# 1_P2.net
KiCad netlist of a schematic drawn in Altium Designer
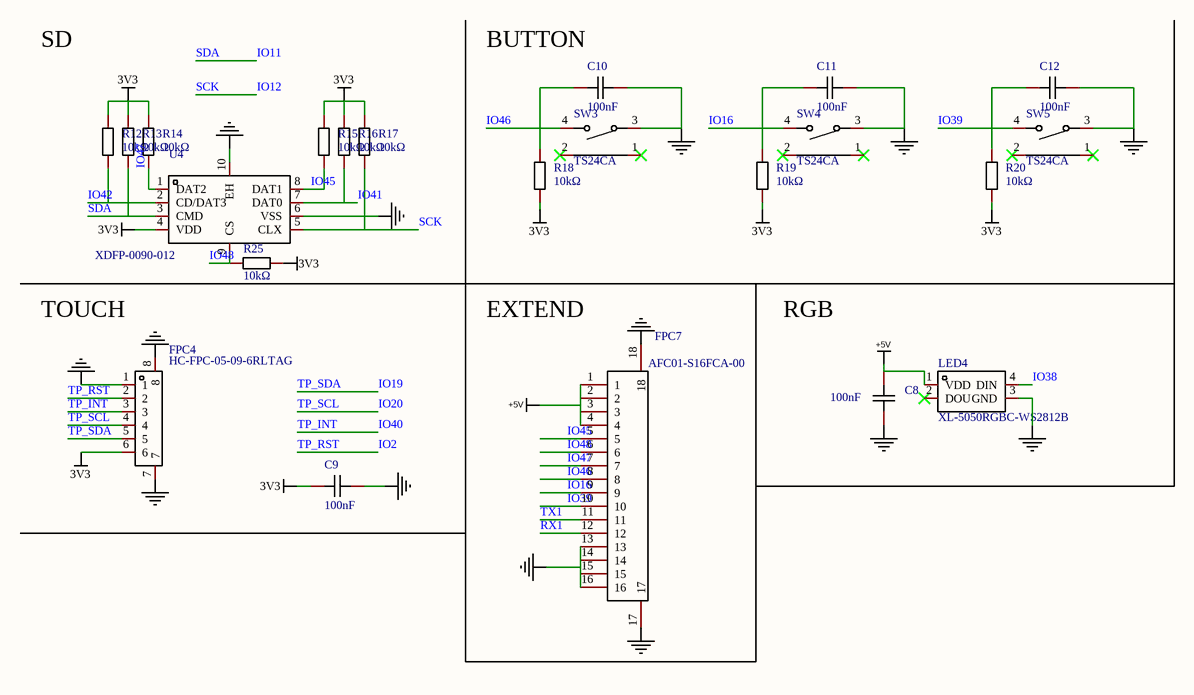
[diagram p0: 1_P2.schdoc]

(export (version "E")
  (design (tool "Eeschema 10.0.6"))
  (components
    (comp (ref "C8")
      (value "100nF")
      (description "容值:100nF;精度:±10%;额定电压:50V;材质(温度系数):X7R;")
      (fields
        (field (name "NAME") "100nF")
        (field (name "MANUFACTURER") "YAGEO(国巨)")
        (field (name "MANUFACTURER PART") "CC0603KRX7R9BB104")
      )
      (libsource (lib "altium-import") (part "root_1_CC0603KRX7R9BB104_"))
    )
    (comp (ref "C9")
      (value "100nF")
      (description "容值:100nF;精度:±10%;额定电压:50V;材质(温度系数):X7R;")
      (fields
        (field (name "NAME") "100nF")
        (field (name "MANUFACTURER") "YAGEO(国巨)")
        (field (name "MANUFACTURER PART") "CC0603KRX7R9BB104")
      )
      (libsource (lib "altium-import") (part "root_2_CC0603KRX7R9BB104_"))
    )
    (comp (ref "C10")
      (value "100nF")
      (description "容值:100nF;精度:±10%;额定电压:50V;材质(温度系数):X7R;")
      (fields
        (field (name "NAME") "100nF")
        (field (name "MANUFACTURER") "YAGEO(国巨)")
        (field (name "MANUFACTURER PART") "CC0603KRX7R9BB104")
      )
      (libsource (lib "altium-import") (part "root_0_CC0603KRX7R9BB104_"))
    )
    (comp (ref "C11")
      (value "100nF")
      (description "容值:100nF;精度:±10%;额定电压:50V;材质(温度系数):X7R;")
      (fields
        (field (name "NAME") "100nF")
        (field (name "MANUFACTURER") "YAGEO(国巨)")
        (field (name "MANUFACTURER PART") "CC0603KRX7R9BB104")
      )
      (libsource (lib "altium-import") (part "root_0_CC0603KRX7R9BB104_"))
    )
    (comp (ref "C12")
      (value "100nF")
      (description "容值:100nF;精度:±10%;额定电压:50V;材质(温度系数):X7R;")
      (fields
        (field (name "NAME") "100nF")
        (field (name "MANUFACTURER") "YAGEO(国巨)")
        (field (name "MANUFACTURER PART") "CC0603KRX7R9BB104")
      )
      (libsource (lib "altium-import") (part "root_0_CC0603KRX7R9BB104_"))
    )
    (comp (ref "FPC4")
      (value "HC-FPC-05-09-6RLTAG")
      (description "锁定特性:翻盖式;触点类型:双侧触点/上下接;触点数量:6P;间距:0.5mm;安装类型:卧贴;工作温度范围:-55℃~+85℃;")
      (fields (field (name "NAME") "HC-FPC-05-09-6RLTAG") (field (name "MANUFACTURER") "HCTL(华灿天禄)"))
      (libsource (lib "altium-import") (part "root_0_HC-FPC-05-09-6RLTAG_"))
    )
    (comp (ref "FPC7")
      (value "AFC01-S16FCA-00")
      (description "锁定特性:翻盖式;触点类型:下接;触点数量:16P;间距:0.5mm;安装类型:卧贴;")
      (fields (field (name "NAME") "AFC01-S16FCA-00") (field (name "MANUFACTURER") "JS(钜硕电子)"))
      (libsource (lib "altium-import") (part "root_0_AFC01-S16FCA-00_"))
    )
    (comp (ref "LED4")
      (value "XL-5050RGBC-WS2812B")
      (description "5050七彩幻彩透明贴片LED灯珠 5050 幻彩透明四脚 ws2812B 内置驱动IC")
      (fields (field (name "NAME") "XL-5050RGBC-WS2812B") (field (name "MANUFACTURER") "XINGLIGHT(成兴光)"))
      (libsource (lib "altium-import") (part "root_0_XL-5050RGBC-WS2812B_"))
    )
    (comp (ref "R12")
      (value "10kΩ")
      (description "电阻类型:厚膜电阻;阻值:10kΩ;精度:±1%;功率:100mW;最大工作电压:75V;温度系数:±100ppm/℃;")
      (fields
        (field (name "NAME") "10kΩ")
        (field (name "MANUFACTURER") "UNI-ROYAL(厚声)")
        (field (name "MANUFACTURER PART") "0603WAF1002T5E")
      )
      (libsource (lib "altium-import") (part "root_1_0603WAF1002T5E_"))
    )
    (comp (ref "R13")
      (value "10kΩ")
      (description "电阻类型:厚膜电阻;阻值:10kΩ;精度:±1%;功率:100mW;最大工作电压:75V;温度系数:±100ppm/℃;")
      (fields
        (field (name "NAME") "10kΩ")
        (field (name "MANUFACTURER") "UNI-ROYAL(厚声)")
        (field (name "MANUFACTURER PART") "0603WAF1002T5E")
      )
      (libsource (lib "altium-import") (part "root_1_0603WAF1002T5E_"))
    )
    (comp (ref "R14")
      (value "10kΩ")
      (description "电阻类型:厚膜电阻;阻值:10kΩ;精度:±1%;功率:100mW;最大工作电压:75V;温度系数:±100ppm/℃;")
      (fields
        (field (name "NAME") "10kΩ")
        (field (name "MANUFACTURER") "UNI-ROYAL(厚声)")
        (field (name "MANUFACTURER PART") "0603WAF1002T5E")
      )
      (libsource (lib "altium-import") (part "root_1_0603WAF1002T5E_"))
    )
    (comp (ref "R15")
      (value "10kΩ")
      (description "电阻类型:厚膜电阻;阻值:10kΩ;精度:±1%;功率:100mW;最大工作电压:75V;温度系数:±100ppm/℃;")
      (fields
        (field (name "NAME") "10kΩ")
        (field (name "MANUFACTURER") "UNI-ROYAL(厚声)")
        (field (name "MANUFACTURER PART") "0603WAF1002T5E")
      )
      (libsource (lib "altium-import") (part "root_1_0603WAF1002T5E_"))
    )
    (comp (ref "R16")
      (value "10kΩ")
      (description "电阻类型:厚膜电阻;阻值:10kΩ;精度:±1%;功率:100mW;最大工作电压:75V;温度系数:±100ppm/℃;")
      (fields
        (field (name "NAME") "10kΩ")
        (field (name "MANUFACTURER") "UNI-ROYAL(厚声)")
        (field (name "MANUFACTURER PART") "0603WAF1002T5E")
      )
      (libsource (lib "altium-import") (part "root_1_0603WAF1002T5E_"))
    )
    (comp (ref "R17")
      (value "10kΩ")
      (description "电阻类型:厚膜电阻;阻值:10kΩ;精度:±1%;功率:100mW;最大工作电压:75V;温度系数:±100ppm/℃;")
      (fields
        (field (name "NAME") "10kΩ")
        (field (name "MANUFACTURER") "UNI-ROYAL(厚声)")
        (field (name "MANUFACTURER PART") "0603WAF1002T5E")
      )
      (libsource (lib "altium-import") (part "root_1_0603WAF1002T5E_"))
    )
    (comp (ref "R18")
      (value "10kΩ")
      (description "电阻类型:厚膜电阻;阻值:10kΩ;精度:±1%;功率:100mW;最大工作电压:75V;温度系数:±100ppm/℃;")
      (fields
        (field (name "NAME") "10kΩ")
        (field (name "MANUFACTURER") "UNI-ROYAL(厚声)")
        (field (name "MANUFACTURER PART") "0603WAF1002T5E")
      )
      (libsource (lib "altium-import") (part "root_1_0603WAF1002T5E_"))
    )
    (comp (ref "R19")
      (value "10kΩ")
      (description "电阻类型:厚膜电阻;阻值:10kΩ;精度:±1%;功率:100mW;最大工作电压:75V;温度系数:±100ppm/℃;")
      (fields
        (field (name "NAME") "10kΩ")
        (field (name "MANUFACTURER") "UNI-ROYAL(厚声)")
        (field (name "MANUFACTURER PART") "0603WAF1002T5E")
      )
      (libsource (lib "altium-import") (part "root_1_0603WAF1002T5E_"))
    )
    (comp (ref "R20")
      (value "10kΩ")
      (description "电阻类型:厚膜电阻;阻值:10kΩ;精度:±1%;功率:100mW;最大工作电压:75V;温度系数:±100ppm/℃;")
      (fields
        (field (name "NAME") "10kΩ")
        (field (name "MANUFACTURER") "UNI-ROYAL(厚声)")
        (field (name "MANUFACTURER PART") "0603WAF1002T5E")
      )
      (libsource (lib "altium-import") (part "root_1_0603WAF1002T5E_"))
    )
    (comp (ref "R25")
      (value "10kΩ")
      (description "电阻类型:厚膜电阻;阻值:10kΩ;精度:±1%;功率:100mW;最大工作电压:75V;温度系数:±100ppm/℃;")
      (fields
        (field (name "NAME") "10kΩ")
        (field (name "MANUFACTURER") "UNI-ROYAL(厚声)")
        (field (name "MANUFACTURER PART") "0603WAF1002T5E")
      )
      (libsource (lib "altium-import") (part "root_2_0603WAF1002T5E_"))
    )
    (comp (ref "SW3")
      (value "TS24CA")
      (description "电路结构:单刀单掷;按钮形状:矩形按钮;安装方式:卧贴;开关长度:4.55mm;开关宽度:1.8mm;开关高度:3.5mm;触点电流:50mA;额定电压(DC):12V;带灯:-;机械寿命:-;")
      (fields (field (name "NAME") "TS24CA") (field (name "MANUFACTURER") "SHOU HAN(首韩)"))
      (libsource (lib "altium-import") (part "root_2_TS24CA_"))
    )
    (comp (ref "SW4")
      (value "TS24CA")
      (description "电路结构:单刀单掷;按钮形状:矩形按钮;安装方式:卧贴;开关长度:4.55mm;开关宽度:1.8mm;开关高度:3.5mm;触点电流:50mA;额定电压(DC):12V;带灯:-;机械寿命:-;")
      (fields (field (name "NAME") "TS24CA") (field (name "MANUFACTURER") "SHOU HAN(首韩)"))
      (libsource (lib "altium-import") (part "root_2_TS24CA_"))
    )
    (comp (ref "SW5")
      (value "TS24CA")
      (description "电路结构:单刀单掷;按钮形状:矩形按钮;安装方式:卧贴;开关长度:4.55mm;开关宽度:1.8mm;开关高度:3.5mm;触点电流:50mA;额定电压(DC):12V;带灯:-;机械寿命:-;")
      (fields (field (name "NAME") "TS24CA") (field (name "MANUFACTURER") "SHOU HAN(首韩)"))
      (libsource (lib "altium-import") (part "root_2_TS24CA_"))
    )
    (comp (ref "U4")
      (value "XDFP-0090-012")
      (description "卡连接方式:自弹式;本体最大高度:1.85mm;触头镀层:金;")
      (fields (field (name "NAME") "XDFP-0090-012") (field (name "MANUFACTURER") "LX(连欣科技)"))
      (libsource (lib "altium-import") (part "root_0_XDFP-0090-012_"))
    )
  )
  (nets
    (net (code "1") (name "+5V") (class "Default")
      (node (ref "C8") (pin "2") (pinfunction "2_2") (pintype "passive"))
      (node (ref "FPC7") (pin "1") (pinfunction "1_1") (pintype "passive"))
      (node (ref "FPC7") (pin "2") (pinfunction "2_2") (pintype "passive"))
      (node (ref "FPC7") (pin "3") (pinfunction "3_3") (pintype "passive"))
      (node (ref "FPC7") (pin "4") (pinfunction "4_4") (pintype "passive"))
      (node (ref "LED4") (pin "1") (pinfunction "VDD_1") (pintype "passive"))
    )
    (net (code "2") (name "/IO2") (class "Default")
      (node (ref "FPC4") (pin "2") (pinfunction "2_2") (pintype "passive"))
    )
    (net (code "3") (name "/IO11") (class "Default")
      (node (ref "R13") (pin "1") (pinfunction "1_1") (pintype "passive"))
      (node (ref "U4") (pin "3") (pinfunction "CMD_3") (pintype "passive"))
    )
    (net (code "4") (name "/IO12") (class "Default")
      (node (ref "R17") (pin "1") (pinfunction "1_1") (pintype "passive"))
      (node (ref "U4") (pin "5") (pinfunction "CLX_5") (pintype "passive"))
    )
    (net (code "5") (name "/IO16") (class "Default")
      (node (ref "C11") (pin "1") (pinfunction "1_1") (pintype "passive"))
      (node (ref "FPC7") (pin "9") (pinfunction "9_9") (pintype "passive"))
      (node (ref "R19") (pin "2") (pinfunction "2_2") (pintype "passive"))
      (node (ref "SW4") (pin "4") (pinfunction "4_4") (pintype "passive"))
    )
    (net (code "6") (name "/IO19") (class "Default")
      (node (ref "FPC4") (pin "5") (pinfunction "5_5") (pintype "passive"))
    )
    (net (code "7") (name "/IO20") (class "Default")
      (node (ref "FPC4") (pin "4") (pinfunction "4_4") (pintype "passive"))
    )
    (net (code "8") (name "/IO38") (class "Default")
      (node (ref "LED4") (pin "4") (pinfunction "DIN_4") (pintype "passive"))
    )
    (net (code "9") (name "/IO39") (class "Default")
      (node (ref "C12") (pin "1") (pinfunction "1_1") (pintype "passive"))
      (node (ref "FPC7") (pin "10") (pinfunction "10_10") (pintype "passive"))
      (node (ref "R20") (pin "2") (pinfunction "2_2") (pintype "passive"))
      (node (ref "SW5") (pin "4") (pinfunction "4_4") (pintype "passive"))
    )
    (net (code "10") (name "/IO40") (class "Default")
      (node (ref "FPC4") (pin "3") (pinfunction "3_3") (pintype "passive"))
    )
    (net (code "11") (name "/IO41") (class "Default")
      (node (ref "R16") (pin "1") (pinfunction "1_1") (pintype "passive"))
      (node (ref "U4") (pin "7") (pinfunction "DAT0_7") (pintype "passive"))
    )
    (net (code "12") (name "/IO42") (class "Default")
      (node (ref "R12") (pin "1") (pinfunction "1_1") (pintype "passive"))
      (node (ref "U4") (pin "2") (pinfunction "CD/DAT3_2") (pintype "passive"))
    )
    (net (code "13") (name "/IO45") (class "Default")
      (node (ref "FPC7") (pin "5") (pinfunction "5_5") (pintype "passive"))
      (node (ref "R15") (pin "1") (pinfunction "1_1") (pintype "passive"))
      (node (ref "U4") (pin "8") (pinfunction "DAT1_8") (pintype "passive"))
    )
    (net (code "14") (name "/IO46") (class "Default")
      (node (ref "C10") (pin "1") (pinfunction "1_1") (pintype "passive"))
      (node (ref "FPC7") (pin "8") (pinfunction "8_8") (pintype "passive"))
      (node (ref "R18") (pin "2") (pinfunction "2_2") (pintype "passive"))
      (node (ref "SW3") (pin "4") (pinfunction "4_4") (pintype "passive"))
    )
    (net (code "15") (name "/IO47") (class "Default")
      (node (ref "FPC7") (pin "7") (pinfunction "7_7") (pintype "passive"))
      (node (ref "R14") (pin "1") (pinfunction "1_1") (pintype "passive"))
      (node (ref "U4") (pin "1") (pinfunction "DAT2_1") (pintype "passive"))
    )
    (net (code "16") (name "/IO48") (class "Default")
      (node (ref "FPC7") (pin "6") (pinfunction "6_6") (pintype "passive"))
      (node (ref "R25") (pin "2") (pinfunction "2_2") (pintype "passive"))
      (node (ref "U4") (pin "9") (pinfunction "CS_9") (pintype "passive"))
    )
    (net (code "17") (name "/RX1") (class "Default")
      (node (ref "FPC7") (pin "12") (pinfunction "12_12") (pintype "passive"))
    )
    (net (code "18") (name "/TX1") (class "Default")
      (node (ref "FPC7") (pin "11") (pinfunction "11_11") (pintype "passive"))
    )
    (net (code "19") (name "3V3") (class "Default")
      (node (ref "C9") (pin "2") (pinfunction "2_2") (pintype "passive"))
      (node (ref "FPC4") (pin "6") (pinfunction "6_6") (pintype "passive"))
      (node (ref "R12") (pin "2") (pinfunction "2_2") (pintype "passive"))
      (node (ref "R13") (pin "2") (pinfunction "2_2") (pintype "passive"))
      (node (ref "R14") (pin "2") (pinfunction "2_2") (pintype "passive"))
      (node (ref "R15") (pin "2") (pinfunction "2_2") (pintype "passive"))
      (node (ref "R16") (pin "2") (pinfunction "2_2") (pintype "passive"))
      (node (ref "R17") (pin "2") (pinfunction "2_2") (pintype "passive"))
      (node (ref "R18") (pin "1") (pinfunction "1_1") (pintype "passive"))
      (node (ref "R19") (pin "1") (pinfunction "1_1") (pintype "passive"))
      (node (ref "R20") (pin "1") (pinfunction "1_1") (pintype "passive"))
      (node (ref "R25") (pin "1") (pinfunction "1_1") (pintype "passive"))
      (node (ref "U4") (pin "4") (pinfunction "VDD_4") (pintype "passive"))
    )
    (net (code "20") (name "<NO NET>") (class "Default")
      (node (ref "C10") (pin "2") (pinfunction "2_2") (pintype "passive"))
      (node (ref "C11") (pin "2") (pinfunction "2_2") (pintype "passive"))
      (node (ref "C12") (pin "2") (pinfunction "2_2") (pintype "passive"))
      (node (ref "C8") (pin "1") (pinfunction "1_1") (pintype "passive"))
      (node (ref "C9") (pin "1") (pinfunction "1_1") (pintype "passive"))
      (node (ref "FPC4") (pin "1") (pinfunction "1_1") (pintype "passive"))
      (node (ref "FPC4") (pin "7") (pinfunction "7_7") (pintype "passive"))
      (node (ref "FPC4") (pin "8") (pinfunction "8_8") (pintype "passive"))
      (node (ref "FPC7") (pin "13") (pinfunction "13_13") (pintype "passive"))
      (node (ref "FPC7") (pin "14") (pinfunction "14_14") (pintype "passive"))
      (node (ref "FPC7") (pin "15") (pinfunction "15_15") (pintype "passive"))
      (node (ref "FPC7") (pin "16") (pinfunction "16_16") (pintype "passive"))
      (node (ref "FPC7") (pin "17") (pinfunction "17_17") (pintype "passive"))
      (node (ref "FPC7") (pin "18") (pinfunction "18_18") (pintype "passive"))
      (node (ref "LED4") (pin "3") (pinfunction "GND_3") (pintype "passive"))
      (node (ref "SW3") (pin "3") (pinfunction "3_3") (pintype "passive"))
      (node (ref "SW4") (pin "3") (pinfunction "3_3") (pintype "passive"))
      (node (ref "SW5") (pin "3") (pinfunction "3_3") (pintype "passive"))
      (node (ref "U4") (pin "10") (pinfunction "EH_10") (pintype "passive"))
      (node (ref "U4") (pin "6") (pinfunction "VSS_6") (pintype "passive"))
    )
    (net (code "21") (name "unconnected-(LED4-DOU-Pad2)") (class "Default")
      (node (ref "LED4") (pin "2") (pinfunction "DOU_2") (pintype "passive+no_connect"))
    )
    (net (code "22") (name "unconnected-(SW3-Pad1)") (class "Default")
      (node (ref "SW3") (pin "1") (pinfunction "1_1") (pintype "passive+no_connect"))
    )
    (net (code "23") (name "unconnected-(SW3-Pad2)") (class "Default")
      (node (ref "SW3") (pin "2") (pinfunction "2_2") (pintype "passive+no_connect"))
    )
    (net (code "24") (name "unconnected-(SW4-Pad1)") (class "Default")
      (node (ref "SW4") (pin "1") (pinfunction "1_1") (pintype "passive+no_connect"))
    )
    (net (code "25") (name "unconnected-(SW4-Pad2)") (class "Default")
      (node (ref "SW4") (pin "2") (pinfunction "2_2") (pintype "passive+no_connect"))
    )
    (net (code "26") (name "unconnected-(SW5-Pad1)") (class "Default")
      (node (ref "SW5") (pin "1") (pinfunction "1_1") (pintype "passive+no_connect"))
    )
    (net (code "27") (name "unconnected-(SW5-Pad2)") (class "Default")
      (node (ref "SW5") (pin "2") (pinfunction "2_2") (pintype "passive+no_connect"))
    )
  )
)
